# Main_Fly_V1_0_0.net
KiCad netlist of a schematic drawn in Altium Designer
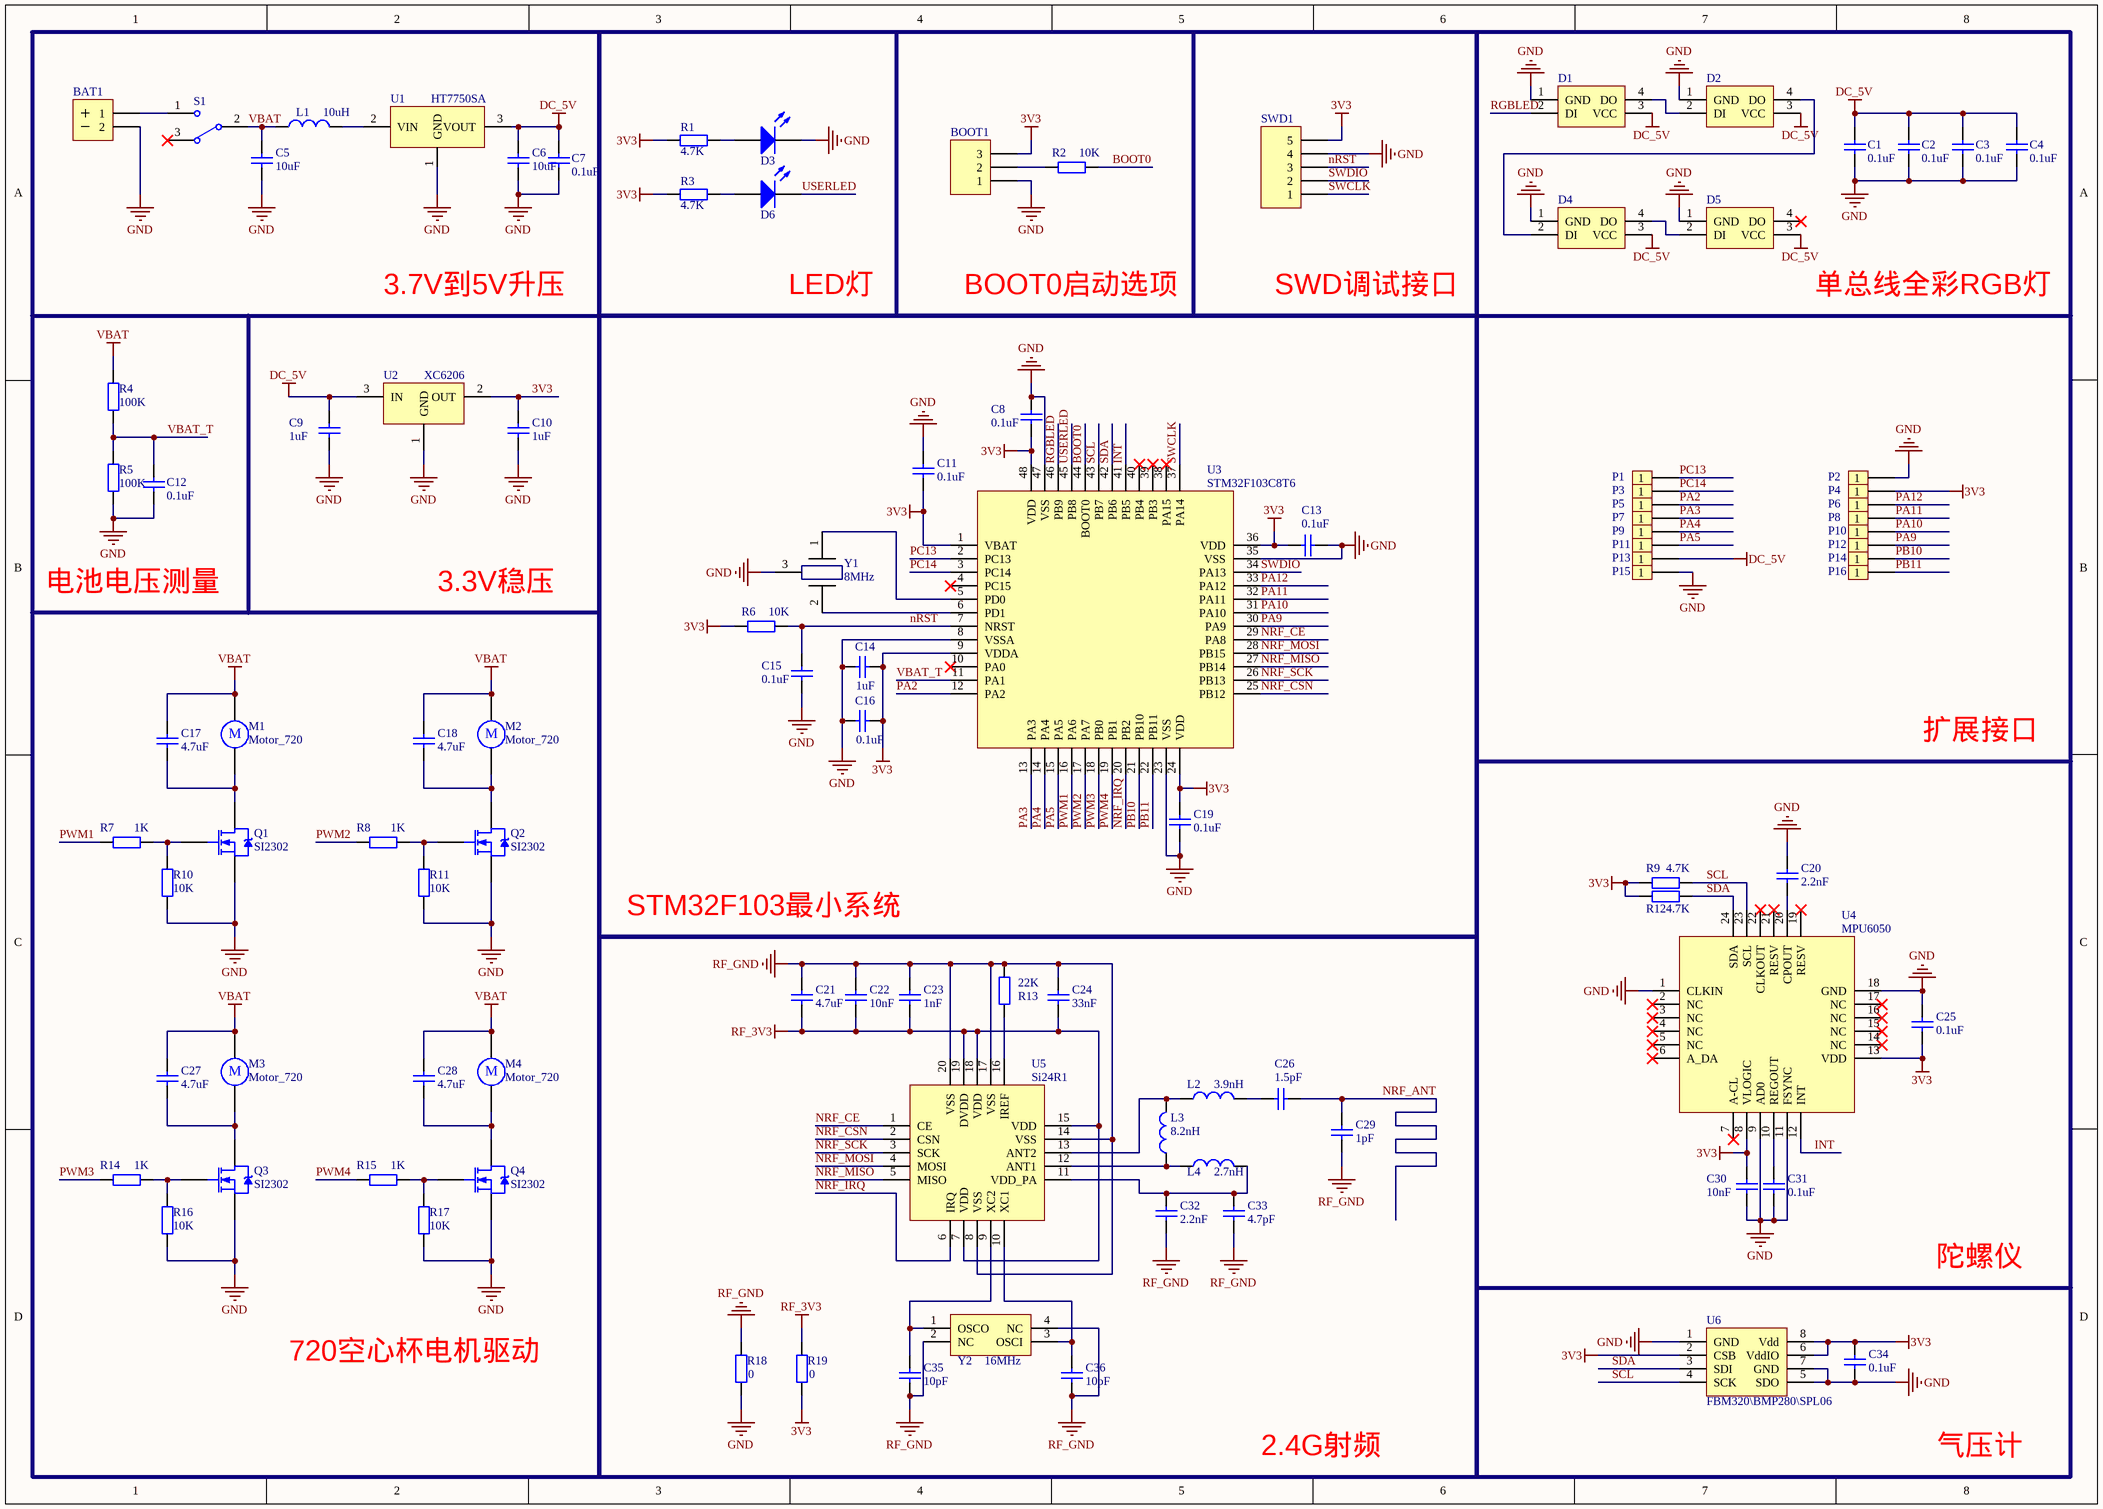
[diagram p0: Main_Fly_V1.0.0.SchDoc]

(export (version "E")
  (design (tool "Eeschema 10.0.6"))
  (components
    (comp (ref "BAT1")
      (value "BAT")
      (footprint "HDR1X2")
      (description "Header, 2-Pin")
      (fields (field (name "PUBLISHER") "mazhongwei"))
      (libsource (lib "RoboFly") (part "BAT"))
    )
    (comp (ref "BOOT1")
      (value "BOOT")
      (footprint "HDR1X3")
      (description "Header, 3-Pin")
      (fields (field (name "PUBLISHER") "Altium Limited"))
      (libsource (lib "RoboFly") (part "Header 3"))
    )
    (comp (ref "C1")
      (value "0.1uF")
      (footprint "C0603")
      (fields (field (name "Comment") "C_0603") (field (name "PUBLISHER") "Altium Limited"))
      (libsource (lib "RoboFly") (part "C_0603"))
    )
    (comp (ref "C2")
      (value "0.1uF")
      (footprint "C0603")
      (fields (field (name "Comment") "C_0603") (field (name "PUBLISHER") "Altium Limited"))
      (libsource (lib "RoboFly") (part "C_0603"))
    )
    (comp (ref "C3")
      (value "0.1uF")
      (footprint "C0603")
      (fields (field (name "Comment") "C_0603") (field (name "PUBLISHER") "Altium Limited"))
      (libsource (lib "RoboFly") (part "C_0603"))
    )
    (comp (ref "C4")
      (value "0.1uF")
      (footprint "C0603")
      (fields (field (name "Comment") "C_0603") (field (name "PUBLISHER") "Altium Limited"))
      (libsource (lib "RoboFly") (part "C_0603"))
    )
    (comp (ref "C5")
      (value "10uF")
      (footprint "C0603")
      (fields (field (name "Comment") "C_0603") (field (name "PUBLISHER") "Altium Limited"))
      (libsource (lib "RoboFly") (part "C_0603"))
    )
    (comp (ref "C6")
      (value "10uF")
      (footprint "C0603")
      (fields (field (name "Comment") "C_0603") (field (name "PUBLISHER") "Altium Limited"))
      (libsource (lib "RoboFly") (part "C_0603"))
    )
    (comp (ref "C7")
      (value "0.1uF")
      (footprint "C0603")
      (fields (field (name "Comment") "C_0603") (field (name "PUBLISHER") "Altium Limited"))
      (libsource (lib "RoboFly") (part "C_0603"))
    )
    (comp (ref "C8")
      (value "0.1uF")
      (footprint "C0603")
      (fields (field (name "Comment") "C_0603") (field (name "PUBLISHER") "Altium Limited"))
      (libsource (lib "RoboFly") (part "C_0603"))
    )
    (comp (ref "C9")
      (value "1uF")
      (footprint "C0603")
      (fields (field (name "Comment") "C_0603") (field (name "PUBLISHER") "Altium Limited"))
      (libsource (lib "RoboFly") (part "C_0603"))
    )
    (comp (ref "C10")
      (value "1uF")
      (footprint "C0603")
      (fields (field (name "Comment") "C_0603") (field (name "PUBLISHER") "Altium Limited"))
      (libsource (lib "RoboFly") (part "C_0603"))
    )
    (comp (ref "C11")
      (value "0.1uF")
      (footprint "C0603")
      (fields (field (name "Comment") "C_0603") (field (name "PUBLISHER") "Altium Limited"))
      (libsource (lib "RoboFly") (part "C_0603"))
    )
    (comp (ref "C12")
      (value "0.1uF")
      (footprint "C0603")
      (fields (field (name "Comment") "C_0603") (field (name "PUBLISHER") "Altium Limited"))
      (libsource (lib "RoboFly") (part "C_0603"))
    )
    (comp (ref "C13")
      (value "0.1uF")
      (footprint "C0603")
      (fields (field (name "Comment") "C_0603") (field (name "PUBLISHER") "Altium Limited"))
      (libsource (lib "RoboFly") (part "C_0603"))
    )
    (comp (ref "C14")
      (value "1uF")
      (footprint "C0603")
      (fields (field (name "Comment") "C_0603") (field (name "PUBLISHER") "Altium Limited"))
      (libsource (lib "RoboFly") (part "C_0603"))
    )
    (comp (ref "C15")
      (value "0.1uF")
      (footprint "C0603")
      (fields (field (name "Comment") "C_0603") (field (name "PUBLISHER") "Altium Limited"))
      (libsource (lib "RoboFly") (part "C_0603"))
    )
    (comp (ref "C16")
      (value "0.1uF")
      (footprint "C0603")
      (fields (field (name "Comment") "C_0603") (field (name "PUBLISHER") "Altium Limited"))
      (libsource (lib "RoboFly") (part "C_0603"))
    )
    (comp (ref "C17")
      (value "4.7uF")
      (footprint "C0603")
      (fields (field (name "Comment") "C_0603") (field (name "PUBLISHER") "Altium Limited"))
      (libsource (lib "RoboFly") (part "C_0603"))
    )
    (comp (ref "C18")
      (value "4.7uF")
      (footprint "C0603")
      (fields (field (name "Comment") "C_0603") (field (name "PUBLISHER") "Altium Limited"))
      (libsource (lib "RoboFly") (part "C_0603"))
    )
    (comp (ref "C19")
      (value "0.1uF")
      (footprint "C0603")
      (fields (field (name "Comment") "C_0603") (field (name "PUBLISHER") "Altium Limited"))
      (libsource (lib "RoboFly") (part "C_0603"))
    )
    (comp (ref "C20")
      (value "2.2nF")
      (footprint "C0603")
      (fields (field (name "Comment") "C_0603") (field (name "PUBLISHER") "Altium Limited"))
      (libsource (lib "RoboFly") (part "C_0603"))
    )
    (comp (ref "C21")
      (value "4.7uF")
      (footprint "C0603")
      (fields (field (name "Comment") "C_0603") (field (name "PUBLISHER") "Altium Limited"))
      (libsource (lib "RoboFly") (part "C_0603"))
    )
    (comp (ref "C22")
      (value "10nF")
      (footprint "C0603")
      (fields (field (name "Comment") "C_0603") (field (name "PUBLISHER") "Altium Limited"))
      (libsource (lib "RoboFly") (part "C_0603"))
    )
    (comp (ref "C23")
      (value "1nF")
      (footprint "C0603")
      (fields (field (name "Comment") "C_0603") (field (name "PUBLISHER") "Altium Limited"))
      (libsource (lib "RoboFly") (part "C_0603"))
    )
    (comp (ref "C24")
      (value "33nF")
      (footprint "C0603")
      (fields (field (name "Comment") "C_0603") (field (name "PUBLISHER") "Altium Limited"))
      (libsource (lib "RoboFly") (part "C_0603"))
    )
    (comp (ref "C25")
      (value "0.1uF")
      (footprint "C0603")
      (fields (field (name "Comment") "C_0603") (field (name "PUBLISHER") "Altium Limited"))
      (libsource (lib "RoboFly") (part "C_0603"))
    )
    (comp (ref "C26")
      (value "1.5pF")
      (footprint "C0603")
      (fields (field (name "Comment") "C_0603") (field (name "PUBLISHER") "Altium Limited"))
      (libsource (lib "RoboFly") (part "C_0603"))
    )
    (comp (ref "C27")
      (value "4.7uF")
      (footprint "C0603")
      (fields (field (name "Comment") "C_0603") (field (name "PUBLISHER") "Altium Limited"))
      (libsource (lib "RoboFly") (part "C_0603"))
    )
    (comp (ref "C28")
      (value "4.7uF")
      (footprint "C0603")
      (fields (field (name "Comment") "C_0603") (field (name "PUBLISHER") "Altium Limited"))
      (libsource (lib "RoboFly") (part "C_0603"))
    )
    (comp (ref "C29")
      (value "1pF")
      (footprint "C0603")
      (fields (field (name "Comment") "C_0603") (field (name "PUBLISHER") "Altium Limited"))
      (libsource (lib "RoboFly") (part "C_0603"))
    )
    (comp (ref "C30")
      (value "10nF")
      (footprint "C0603")
      (fields (field (name "Comment") "C_0603") (field (name "PUBLISHER") "Altium Limited"))
      (libsource (lib "RoboFly") (part "C_0603"))
    )
    (comp (ref "C31")
      (value "0.1uF")
      (footprint "C0603")
      (fields (field (name "Comment") "C_0603") (field (name "PUBLISHER") "Altium Limited"))
      (libsource (lib "RoboFly") (part "C_0603"))
    )
    (comp (ref "C32")
      (value "2.2nF")
      (footprint "C0603")
      (fields (field (name "Comment") "C_0603") (field (name "PUBLISHER") "Altium Limited"))
      (libsource (lib "RoboFly") (part "C_0603"))
    )
    (comp (ref "C33")
      (value "4.7pF")
      (footprint "C0603")
      (fields (field (name "Comment") "C_0603") (field (name "PUBLISHER") "Altium Limited"))
      (libsource (lib "RoboFly") (part "C_0603"))
    )
    (comp (ref "C34")
      (value "0.1uF")
      (footprint "C0603")
      (fields (field (name "Comment") "C_0603") (field (name "PUBLISHER") "Altium Limited"))
      (libsource (lib "RoboFly") (part "C_0603"))
    )
    (comp (ref "C35")
      (value "10pF")
      (footprint "C0603")
      (fields (field (name "Comment") "C_0603") (field (name "PUBLISHER") "Altium Limited"))
      (libsource (lib "RoboFly") (part "C_0603"))
    )
    (comp (ref "C36")
      (value "10pF")
      (footprint "C0603")
      (fields (field (name "Comment") "C_0603") (field (name "PUBLISHER") "Altium Limited"))
      (libsource (lib "RoboFly") (part "C_0603"))
    )
    (comp (ref "D1")
      (value "P923D")
      (footprint "RGB_LED_5050")
      (fields (field (name "PUBLISHER") "mazhongwei"))
      (libsource (lib "RoboFly") (part "P923D"))
    )
    (comp (ref "D2")
      (value "P923D")
      (footprint "RGB_LED_5050")
      (fields (field (name "PUBLISHER") "mazhongwei"))
      (libsource (lib "RoboFly") (part "P923D"))
    )
    (comp (ref "D3")
      (value "LED_0603")
      (footprint "LED0603-green")
      (description "发光二极管")
      (fields (field (name "PUBLISHER") "Altium Limited"))
      (libsource (lib "RoboFly") (part "LED 0603"))
    )
    (comp (ref "D4")
      (value "P923D")
      (footprint "RGB_LED_5050")
      (fields (field (name "PUBLISHER") "mazhongwei"))
      (libsource (lib "RoboFly") (part "P923D"))
    )
    (comp (ref "D5")
      (value "P923D")
      (footprint "RGB_LED_5050")
      (fields (field (name "PUBLISHER") "mazhongwei"))
      (libsource (lib "RoboFly") (part "P923D"))
    )
    (comp (ref "D6")
      (value "LED_0603")
      (footprint "LED0603-green")
      (description "发光二极管")
      (fields (field (name "PUBLISHER") "Altium Limited"))
      (libsource (lib "RoboFly") (part "LED 0603"))
    )
    (comp (ref "L1")
      (value "10uH")
      (footprint "L_1812")
      (description "电感")
      (fields (field (name "Comment") "Inductor") (field (name "PUBLISHER") "Altium Limited"))
      (libsource (lib "RoboFly") (part "Inductor"))
    )
    (comp (ref "L2")
      (value "3.9nH")
      (footprint "C0603")
      (description "电感")
      (fields (field (name "Comment") "Inductor") (field (name "PUBLISHER") "Altium Limited"))
      (libsource (lib "RoboFly") (part "Inductor_1"))
    )
    (comp (ref "L3")
      (value "8.2nH")
      (footprint "C0603")
      (description "电感")
      (fields (field (name "Comment") "Inductor") (field (name "PUBLISHER") "Altium Limited"))
      (libsource (lib "RoboFly") (part "Inductor_1"))
    )
    (comp (ref "L4")
      (value "2.7nH")
      (footprint "C0603")
      (description "电感")
      (fields (field (name "Comment") "Inductor") (field (name "PUBLISHER") "Altium Limited"))
      (libsource (lib "RoboFly") (part "Inductor_1"))
    )
    (comp (ref "M1")
      (value "Motor_720")
      (footprint "MOTOR")
      (description "Motor, General Kind")
      (fields (field (name "PUBLISHER") "mazhongwei"))
      (libsource (lib "RoboFly") (part "Motor_720"))
    )
    (comp (ref "M2")
      (value "Motor_720")
      (footprint "MOTOR")
      (description "Motor, General Kind")
      (fields (field (name "PUBLISHER") "mazhongwei"))
      (libsource (lib "RoboFly") (part "Motor_720"))
    )
    (comp (ref "M3")
      (value "Motor_720")
      (footprint "MOTOR")
      (description "Motor, General Kind")
      (fields (field (name "PUBLISHER") "mazhongwei"))
      (libsource (lib "RoboFly") (part "Motor_720"))
    )
    (comp (ref "M4")
      (value "Motor_720")
      (footprint "MOTOR")
      (description "Motor, General Kind")
      (fields (field (name "PUBLISHER") "mazhongwei"))
      (libsource (lib "RoboFly") (part "Motor_720"))
    )
    (comp (ref "P1")
      (value "Header 1")
      (footprint "HEADER1")
      (fields (field (name "PUBLISHER") "Altium Limited"))
      (libsource (lib "RoboFly") (part "Header 1"))
    )
    (comp (ref "P2")
      (value "Header 1")
      (footprint "HEADER1")
      (fields (field (name "PUBLISHER") "Altium Limited"))
      (libsource (lib "RoboFly") (part "Header 1"))
    )
    (comp (ref "P3")
      (value "Header 1")
      (footprint "HEADER1")
      (fields (field (name "PUBLISHER") "Altium Limited"))
      (libsource (lib "RoboFly") (part "Header 1"))
    )
    (comp (ref "P4")
      (value "Header 1")
      (footprint "HEADER1")
      (fields (field (name "PUBLISHER") "Altium Limited"))
      (libsource (lib "RoboFly") (part "Header 1"))
    )
    (comp (ref "P5")
      (value "Header 1")
      (footprint "HEADER1")
      (fields (field (name "PUBLISHER") "Altium Limited"))
      (libsource (lib "RoboFly") (part "Header 1"))
    )
    (comp (ref "P6")
      (value "Header 1")
      (footprint "HEADER1")
      (fields (field (name "PUBLISHER") "Altium Limited"))
      (libsource (lib "RoboFly") (part "Header 1"))
    )
    (comp (ref "P7")
      (value "Header 1")
      (footprint "HEADER1")
      (fields (field (name "PUBLISHER") "Altium Limited"))
      (libsource (lib "RoboFly") (part "Header 1"))
    )
    (comp (ref "P8")
      (value "Header 1")
      (footprint "HEADER1")
      (fields (field (name "PUBLISHER") "Altium Limited"))
      (libsource (lib "RoboFly") (part "Header 1"))
    )
    (comp (ref "P9")
      (value "Header 1")
      (footprint "HEADER1")
      (fields (field (name "PUBLISHER") "Altium Limited"))
      (libsource (lib "RoboFly") (part "Header 1"))
    )
    (comp (ref "P10")
      (value "Header 1")
      (footprint "HEADER1")
      (fields (field (name "PUBLISHER") "Altium Limited"))
      (libsource (lib "RoboFly") (part "Header 1"))
    )
    (comp (ref "P11")
      (value "Header 1")
      (footprint "HEADER1")
      (fields (field (name "PUBLISHER") "Altium Limited"))
      (libsource (lib "RoboFly") (part "Header 1"))
    )
    (comp (ref "P12")
      (value "Header 1")
      (footprint "HEADER1")
      (fields (field (name "PUBLISHER") "Altium Limited"))
      (libsource (lib "RoboFly") (part "Header 1"))
    )
    (comp (ref "P13")
      (value "Header 1")
      (footprint "HEADER1")
      (fields (field (name "PUBLISHER") "Altium Limited"))
      (libsource (lib "RoboFly") (part "Header 1"))
    )
    (comp (ref "P14")
      (value "Header 1")
      (footprint "HEADER1")
      (fields (field (name "PUBLISHER") "Altium Limited"))
      (libsource (lib "RoboFly") (part "Header 1"))
    )
    (comp (ref "P15")
      (value "Header 1")
      (footprint "HEADER1")
      (fields (field (name "PUBLISHER") "Altium Limited"))
      (libsource (lib "RoboFly") (part "Header 1"))
    )
    (comp (ref "P16")
      (value "Header 1")
      (footprint "HEADER1")
      (fields (field (name "PUBLISHER") "Altium Limited"))
      (libsource (lib "RoboFly") (part "Header 1"))
    )
    (comp (ref "Q1")
      (value "SI2302")
      (footprint "SOT-23-3")
      (description "N-Channel Power MOSFET")
      (fields (field (name "PUBLISHER") "mazhongwei"))
      (libsource (lib "RoboFly") (part "SI2302"))
    )
    (comp (ref "Q2")
      (value "SI2302")
      (footprint "SOT-23-3")
      (description "N-Channel Power MOSFET")
      (fields (field (name "PUBLISHER") "mazhongwei"))
      (libsource (lib "RoboFly") (part "SI2302"))
    )
    (comp (ref "Q3")
      (value "SI2302")
      (footprint "SOT-23-3")
      (description "N-Channel Power MOSFET")
      (fields (field (name "PUBLISHER") "mazhongwei"))
      (libsource (lib "RoboFly") (part "SI2302"))
    )
    (comp (ref "Q4")
      (value "SI2302")
      (footprint "SOT-23-3")
      (description "N-Channel Power MOSFET")
      (fields (field (name "PUBLISHER") "mazhongwei"))
      (libsource (lib "RoboFly") (part "SI2302"))
    )
    (comp (ref "R1")
      (value "4.7K")
      (footprint "R0603 - 1")
      (fields (field (name "Comment") "R_0603") (field (name "PUBLISHER") "Altium Limited"))
      (libsource (lib "RoboFly") (part "R_0603"))
    )
    (comp (ref "R2")
      (value "10K")
      (footprint "R0603 - 1")
      (fields (field (name "Comment") "R_0603") (field (name "PUBLISHER") "Altium Limited"))
      (libsource (lib "RoboFly") (part "R_0603"))
    )
    (comp (ref "R3")
      (value "4.7K")
      (footprint "R0603 - 1")
      (fields (field (name "Comment") "R_0603") (field (name "PUBLISHER") "Altium Limited"))
      (libsource (lib "RoboFly") (part "R_0603"))
    )
    (comp (ref "R4")
      (value "100K")
      (footprint "R0603 - 1")
      (fields (field (name "Comment") "R_0603") (field (name "PUBLISHER") "Altium Limited"))
      (libsource (lib "") (part "R_0603_1"))
    )
    (comp (ref "R5")
      (value "100K")
      (footprint "R0603 - 1")
      (fields (field (name "Comment") "R_0603") (field (name "PUBLISHER") "Altium Limited"))
      (libsource (lib "") (part "R_0603_1"))
    )
    (comp (ref "R6")
      (value "10K")
      (footprint "R0603 - 1")
      (fields (field (name "Comment") "R_0603") (field (name "PUBLISHER") "Altium Limited"))
      (libsource (lib "") (part "R_0603_2"))
    )
    (comp (ref "R7")
      (value "1K")
      (footprint "R0603 - 1")
      (fields (field (name "Comment") "R_0603") (field (name "PUBLISHER") "Altium Limited"))
      (libsource (lib "RoboFly") (part "R_0603"))
    )
    (comp (ref "R8")
      (value "1K")
      (footprint "R0603 - 1")
      (fields (field (name "Comment") "R_0603") (field (name "PUBLISHER") "Altium Limited"))
      (libsource (lib "RoboFly") (part "R_0603"))
    )
    (comp (ref "R9")
      (value "4.7K")
      (footprint "R0603 - 1")
      (fields (field (name "Comment") "R_0603") (field (name "PUBLISHER") "Altium Limited"))
      (libsource (lib "RoboFly") (part "R_0603"))
    )
    (comp (ref "R10")
      (value "10K")
      (footprint "R0603 - 1")
      (fields (field (name "Comment") "R_0603") (field (name "PUBLISHER") "Altium Limited"))
      (libsource (lib "") (part "R_0603_1"))
    )
    (comp (ref "R11")
      (value "10K")
      (footprint "R0603 - 1")
      (fields (field (name "Comment") "R_0603") (field (name "PUBLISHER") "Altium Limited"))
      (libsource (lib "") (part "R_0603_1"))
    )
    (comp (ref "R12")
      (value "4.7K")
      (footprint "R0603 - 1")
      (fields (field (name "Comment") "R_0603") (field (name "PUBLISHER") "Altium Limited"))
      (libsource (lib "RoboFly") (part "R_0603"))
    )
    (comp (ref "R13")
      (value "22K")
      (footprint "R0603 - 1")
      (fields (field (name "Comment") "R_0603") (field (name "PUBLISHER") "Altium Limited"))
      (libsource (lib "") (part "R_0603_1"))
    )
    (comp (ref "R14")
      (value "1K")
      (footprint "R0603 - 1")
      (fields (field (name "Comment") "R_0603") (field (name "PUBLISHER") "Altium Limited"))
      (libsource (lib "RoboFly") (part "R_0603"))
    )
    (comp (ref "R15")
      (value "1K")
      (footprint "R0603 - 1")
      (fields (field (name "Comment") "R_0603") (field (name "PUBLISHER") "Altium Limited"))
      (libsource (lib "RoboFly") (part "R_0603"))
    )
    (comp (ref "R16")
      (value "10K")
      (footprint "R0603 - 1")
      (fields (field (name "Comment") "R_0603") (field (name "PUBLISHER") "Altium Limited"))
      (libsource (lib "") (part "R_0603_1"))
    )
    (comp (ref "R17")
      (value "10K")
      (footprint "R0603 - 1")
      (fields (field (name "Comment") "R_0603") (field (name "PUBLISHER") "Altium Limited"))
      (libsource (lib "") (part "R_0603_1"))
    )
    (comp (ref "R18")
      (value "0")
      (footprint "R0603 - 1")
      (fields (field (name "Comment") "R_0603") (field (name "PUBLISHER") "Altium Limited"))
      (libsource (lib "新版四轴飞行器") (part "R_0603"))
    )
    (comp (ref "R19")
      (value "0")
      (footprint "R0603 - 1")
      (fields (field (name "Comment") "R_0603") (field (name "PUBLISHER") "Altium Limited"))
      (libsource (lib "新版四轴飞行器") (part "R_0603"))
    )
    (comp (ref "S1")
      (value "SW-SPDT")
      (footprint "SWITCH_PWR")
      (description "SPDT Subminiature Toggle Switch, Right Angle Mounting, Vertical Actuation")
      (fields (field (name "PUBLISHER") "mazhongwei"))
      (libsource (lib "RoboFly") (part "SW-SPDT"))
    )
    (comp (ref "SWD1")
      (value "SWD")
      (footprint "HDR1X5")
      (description "Header, 5-Pin")
      (fields (field (name "PUBLISHER") "Altium Limited"))
      (libsource (lib "RoboFly") (part "Header 5"))
    )
    (comp (ref "U1")
      (value "HT7750SA")
      (footprint "SOT-89(SOT-89-3)")
      (libsource (lib "RoboFly") (part "HT7750SA"))
    )
    (comp (ref "U2")
      (value "XC6206")
      (footprint "SOT-23-3")
      (fields (field (name "PUBLISHER") "mazhongwei"))
      (libsource (lib "RoboFly") (part "XC6206"))
    )
    (comp (ref "U3")
      (value "STM32F103C8T6")
      (footprint "LC-LQFP-48_7x7x05P")
      (libsource (lib "RoboFly") (part "STM32F103C8T6"))
    )
    (comp (ref "U4")
      (value "MPU6050")
      (footprint "QFN-24_4x4x05P")
      (libsource (lib "RoboFly") (part "MPU6050"))
    )
    (comp (ref "U5") (value "Si24R1") (footprint "QFN-20_4x4") (libsource (lib "RoboFly") (part "nRF24L01")))
    (comp (ref "U6")
      (value "FBM32~{0}BMP28~{0}SPL06")
      (footprint "LGA-2_5X2MM")
      (description "气压计")
      (fields (field (name "PUBLISHER") "mazhongwei"))
      (libsource (lib "RoboFly") (part "FBM320"))
    )
    (comp (ref "Y1")
      (value "8MHz")
      (footprint "SMD-cstse800G52-r0")
      (fields (field (name "Comment") "XTAL") (field (name "PUBLISHER") "mazhongwei"))
      (libsource (lib "RoboFly") (part "XTAL_2"))
    )
    (comp (ref "Y2")
      (value "16MHz")
      (footprint "CRYSTAL_RSX-10")
      (description "XTAL16M")
      (fields (field (name "Comment") "XTAL"))
      (libsource (lib "RoboFly") (part "XTAL16M"))
    )
  )
  (nets
    (net (code "1") (name "/BOOT0") (class "Default")
      (node (ref "R2") (pin "2") (pinfunction "2_2") (pintype "passive"))
      (node (ref "U3") (pin "44") (pinfunction "BOOT0_44") (pintype "passive"))
    )
    (net (code "2") (name "/INT") (class "Default")
      (node (ref "U3") (pin "41") (pinfunction "PB5_41") (pintype "passive"))
      (node (ref "U4") (pin "12") (pinfunction "INT_12") (pintype "passive"))
    )
    (net (code "3") (name "/NRF_ANT") (class "Default")
      (node (ref "C26") (pin "2") (pinfunction "2_2") (pintype "passive"))
      (node (ref "C29") (pin "2") (pinfunction "2_2") (pintype "passive"))
    )
    (net (code "4") (name "/NRF_CE") (class "Default")
      (node (ref "U3") (pin "29") (pinfunction "PA8_29") (pintype "passive"))
      (node (ref "U5") (pin "1") (pinfunction "CE_1") (pintype "passive"))
    )
    (net (code "5") (name "/NRF_CSN") (class "Default")
      (node (ref "U3") (pin "25") (pinfunction "PB12_25") (pintype "passive"))
      (node (ref "U5") (pin "2") (pinfunction "CSN_2") (pintype "passive"))
    )
    (net (code "6") (name "/NRF_IRQ") (class "Default")
      (node (ref "U3") (pin "20") (pinfunction "PB2_20") (pintype "passive"))
      (node (ref "U5") (pin "6") (pinfunction "IRQ_6") (pintype "passive"))
    )
    (net (code "7") (name "/NRF_MISO") (class "Default")
      (node (ref "U3") (pin "27") (pinfunction "PB14_27") (pintype "passive"))
      (node (ref "U5") (pin "5") (pinfunction "MISO_5") (pintype "passive"))
    )
    (net (code "8") (name "/NRF_MOSI") (class "Default")
      (node (ref "U3") (pin "28") (pinfunction "PB15_28") (pintype "passive"))
      (node (ref "U5") (pin "4") (pinfunction "MOSI_4") (pintype "passive"))
    )
    (net (code "9") (name "/NRF_SCK") (class "Default")
      (node (ref "U3") (pin "26") (pinfunction "PB13_26") (pintype "passive"))
      (node (ref "U5") (pin "3") (pinfunction "SCK_3") (pintype "passive"))
    )
    (net (code "10") (name "/PA2") (class "Default")
      (node (ref "P5") (pin "1") (pinfunction "1_1") (pintype "passive"))
      (node (ref "U3") (pin "12") (pinfunction "PA2_12") (pintype "passive"))
    )
    (net (code "11") (name "/PA3") (class "Default")
      (node (ref "P7") (pin "1") (pinfunction "1_1") (pintype "passive"))
      (node (ref "U3") (pin "13") (pinfunction "PA3_13") (pintype "passive"))
    )
    (net (code "12") (name "/PA4") (class "Default")
      (node (ref "P9") (pin "1") (pinfunction "1_1") (pintype "passive"))
      (node (ref "U3") (pin "14") (pinfunction "PA4_14") (pintype "passive"))
    )
    (net (code "13") (name "/PA5") (class "Default")
      (node (ref "P11") (pin "1") (pinfunction "1_1") (pintype "passive"))
      (node (ref "U3") (pin "15") (pinfunction "PA5_15") (pintype "passive"))
    )
    (net (code "14") (name "/PA9") (class "Default")
      (node (ref "P12") (pin "1") (pinfunction "1_1") (pintype "passive"))
      (node (ref "U3") (pin "30") (pinfunction "PA9_30") (pintype "passive"))
    )
    (net (code "15") (name "/PA10") (class "Default")
      (node (ref "P10") (pin "1") (pinfunction "1_1") (pintype "passive"))
      (node (ref "U3") (pin "31") (pinfunction "PA10_31") (pintype "passive"))
    )
    (net (code "16") (name "/PA11") (class "Default")
      (node (ref "P8") (pin "1") (pinfunction "1_1") (pintype "passive"))
      (node (ref "U3") (pin "32") (pinfunction "PA11_32") (pintype "passive"))
    )
    (net (code "17") (name "/PA12") (class "Default")
      (node (ref "P6") (pin "1") (pinfunction "1_1") (pintype "passive"))
      (node (ref "U3") (pin "33") (pinfunction "PA12_33") (pintype "passive"))
    )
    (net (code "18") (name "/PB10") (class "Default")
      (node (ref "P14") (pin "1") (pinfunction "1_1") (pintype "passive"))
      (node (ref "U3") (pin "21") (pinfunction "PB10_21") (pintype "passive"))
    )
    (net (code "19") (name "/PB11") (class "Default")
      (node (ref "P16") (pin "1") (pinfunction "1_1") (pintype "passive"))
      (node (ref "U3") (pin "22") (pinfunction "PB11_22") (pintype "passive"))
    )
    (net (code "20") (name "/PC13") (class "Default")
      (node (ref "P1") (pin "1") (pinfunction "1_1") (pintype "passive"))
      (node (ref "U3") (pin "2") (pinfunction "PC13_2") (pintype "passive"))
    )
    (net (code "21") (name "/PC14") (class "Default")
      (node (ref "P3") (pin "1") (pinfunction "1_1") (pintype "passive"))
      (node (ref "U3") (pin "3") (pinfunction "PC14_3") (pintype "passive"))
    )
    (net (code "22") (name "/PWM1") (class "Default")
      (node (ref "R7") (pin "1") (pinfunction "1_1") (pintype "passive"))
      (node (ref "U3") (pin "16") (pinfunction "PA6_16") (pintype "passive"))
    )
    (net (code "23") (name "/PWM2") (class "Default")
      (node (ref "R8") (pin "1") (pinfunction "1_1") (pintype "passive"))
      (node (ref "U3") (pin "17") (pinfunction "PA7_17") (pintype "passive"))
    )
    (net (code "24") (name "/PWM3") (class "Default")
      (node (ref "R14") (pin "1") (pinfunction "1_1") (pintype "passive"))
      (node (ref "U3") (pin "18") (pinfunction "PB0_18") (pintype "passive"))
    )
    (net (code "25") (name "/PWM4") (class "Default")
      (node (ref "R15") (pin "1") (pinfunction "1_1") (pintype "passive"))
      (node (ref "U3") (pin "19") (pinfunction "PB1_19") (pintype "passive"))
    )
    (net (code "26") (name "/RGBLED") (class "Default")
      (node (ref "D1") (pin "2") (pinfunction "DI_2") (pintype "passive"))
      (node (ref "U3") (pin "46") (pinfunction "PB9_46") (pintype "passive"))
    )
    (net (code "27") (name "/SCL") (class "Default")
      (node (ref "R9") (pin "2") (pinfunction "2_2") (pintype "passive"))
      (node (ref "U3") (pin "43") (pinfunction "PB7_43") (pintype "passive"))
      (node (ref "U4") (pin "23") (pinfunction "SCL_23") (pintype "passive"))
      (node (ref "U6") (pin "4") (pinfunction "SCK_4") (pintype "passive"))
    )
    (net (code "28") (name "/SDA") (class "Default")
      (node (ref "R12") (pin "2") (pinfunction "2_2") (pintype "passive"))
      (node (ref "U3") (pin "42") (pinfunction "PB6_42") (pintype "passive"))
      (node (ref "U4") (pin "24") (pinfunction "SDA_24") (pintype "passive"))
      (node (ref "U6") (pin "3") (pinfunction "SDI_3") (pintype "passive"))
    )
    (net (code "29") (name "/SWCLK") (class "Default")
      (node (ref "SWD1") (pin "1") (pinfunction "1_1") (pintype "passive"))
      (node (ref "U3") (pin "37") (pinfunction "PA14_37") (pintype "passive"))
    )
    (net (code "30") (name "/SWDIO") (class "Default")
      (node (ref "SWD1") (pin "2") (pinfunction "2_2") (pintype "passive"))
      (node (ref "U3") (pin "34") (pinfunction "PA13_34") (pintype "passive"))
    )
    (net (code "31") (name "/USERLED") (class "Default")
      (node (ref "D6") (pin "2") (pinfunction "2_2") (pintype "passive"))
      (node (ref "U3") (pin "45") (pinfunction "PB8_45") (pintype "passive"))
    )
    (net (code "32") (name "/VBAT_T") (class "Default")
      (node (ref "C12") (pin "2") (pinfunction "2_2") (pintype "passive"))
      (node (ref "R4") (pin "1") (pinfunction "1_1") (pintype "passive"))
      (node (ref "R5") (pin "2") (pinfunction "2_2") (pintype "passive"))
      (node (ref "U3") (pin "11") (pinfunction "PA1_11") (pintype "passive"))
    )
    (net (code "33") (name "/nRST") (class "Default")
      (node (ref "C15") (pin "2") (pinfunction "2_2") (pintype "passive"))
      (node (ref "R6") (pin "1") (pinfunction "1_1") (pintype "passive"))
      (node (ref "SWD1") (pin "3") (pinfunction "3_3") (pintype "passive"))
      (node (ref "U3") (pin "7") (pinfunction "NRST_7") (pintype "passive"))
    )
    (net (code "34") (name "3V3") (class "Default")
      (node (ref "BOOT1") (pin "3") (pinfunction "3_3") (pintype "passive"))
      (node (ref "C10") (pin "1") (pinfunction "1_1") (pintype "passive"))
      (node (ref "C11") (pin "2") (pinfunction "2_2") (pintype "passive"))
      (node (ref "C13") (pin "2") (pinfunction "2_2") (pintype "passive"))
      (node (ref "C14") (pin "2") (pinfunction "2_2") (pintype "passive"))
      (node (ref "C16") (pin "2") (pinfunction "2_2") (pintype "passive"))
      (node (ref "C19") (pin "1") (pinfunction "1_1") (pintype "passive"))
      (node (ref "C25") (pin "2") (pinfunction "2_2") (pintype "passive"))
      (node (ref "C30") (pin "2") (pinfunction "2_2") (pintype "passive"))
      (node (ref "C34") (pin "1") (pinfunction "1_1") (pintype "passive"))
      (node (ref "C8") (pin "1") (pinfunction "1_1") (pintype "passive"))
      (node (ref "P4") (pin "1") (pinfunction "1_1") (pintype "passive"))
      (node (ref "R1") (pin "1") (pinfunction "1_1") (pintype "passive"))
      (node (ref "R12") (pin "1") (pinfunction "1_1") (pintype "passive"))
      (node (ref "R19") (pin "1") (pinfunction "1_1") (pintype "passive"))
      (node (ref "R3") (pin "1") (pinfunction "1_1") (pintype "passive"))
      (node (ref "R6") (pin "2") (pinfunction "2_2") (pintype "passive"))
      (node (ref "R9") (pin "1") (pinfunction "1_1") (pintype "passive"))
      (node (ref "SWD1") (pin "5") (pinfunction "5_5") (pintype "passive"))
      (node (ref "U2") (pin "2") (pinfunction "OUT_2") (pintype "passive"))
      (node (ref "U3") (pin "1") (pinfunction "VBAT_1") (pintype "passive"))
      (node (ref "U3") (pin "24") (pinfunction "VDD_24") (pintype "passive"))
      (node (ref "U3") (pin "36") (pinfunction "VDD_36") (pintype "passive"))
      (node (ref "U3") (pin "48") (pinfunction "VDD_48") (pintype "passive"))
      (node (ref "U3") (pin "9") (pinfunction "VDDA_9") (pintype "passive"))
      (node (ref "U4") (pin "13") (pinfunction "VDD_13") (pintype "passive"))
      (node (ref "U4") (pin "8") (pinfunction "VLOGIC_8") (pintype "passive"))
      (node (ref "U6") (pin "2") (pinfunction "CSB_2") (pintype "passive"))
      (node (ref "U6") (pin "6") (pinfunction "VddIO_6") (pintype "passive"))
      (node (ref "U6") (pin "8") (pinfunction "Vdd_8") (pintype "passive"))
    )
    (net (code "35") (name "DC_5V") (class "Default")
      (node (ref "C1") (pin "2") (pinfunction "2_2") (pintype "passive"))
      (node (ref "C2") (pin "2") (pinfunction "2_2") (pintype "passive"))
      (node (ref "C3") (pin "2") (pinfunction "2_2") (pintype "passive"))
      (node (ref "C4") (pin "2") (pinfunction "2_2") (pintype "passive"))
      (node (ref "C6") (pin "1") (pinfunction "1_1") (pintype "passive"))
      (node (ref "C7") (pin "2") (pinfunction "2_2") (pintype "passive"))
      (node (ref "C9") (pin "2") (pinfunction "2_2") (pintype "passive"))
      (node (ref "D1") (pin "3") (pinfunction "VCC_3") (pintype "passive"))
      (node (ref "D2") (pin "3") (pinfunction "VCC_3") (pintype "passive"))
      (node (ref "D4") (pin "3") (pinfunction "VCC_3") (pintype "passive"))
      (node (ref "D5") (pin "3") (pinfunction "VCC_3") (pintype "passive"))
      (node (ref "P13") (pin "1") (pinfunction "1_1") (pintype "passive"))
      (node (ref "U1") (pin "3") (pinfunction "VOUT_3") (pintype "passive"))
      (node (ref "U2") (pin "3") (pinfunction "IN_3") (pintype "passive"))
    )
    (net (code "36") (name "GND") (class "Default")
      (node (ref "BAT1") (pin "2") (pinfunction "2_2") (pintype "passive"))
      (node (ref "BOOT1") (pin "1") (pinfunction "1_1") (pintype "passive"))
      (node (ref "C1") (pin "1") (pinfunction "1_1") (pintype "passive"))
      (node (ref "C10") (pin "2") (pinfunction "2_2") (pintype "passive"))
      (node (ref "C11") (pin "1") (pinfunction "1_1") (pintype "passive"))
      (node (ref "C12") (pin "1") (pinfunction "1_1") (pintype "passive"))
      (node (ref "C13") (pin "1") (pinfunction "1_1") (pintype "passive"))
      (node (ref "C14") (pin "1") (pinfunction "1_1") (pintype "passive"))
      (node (ref "C15") (pin "1") (pinfunction "1_1") (pintype "passive"))
      (node (ref "C16") (pin "1") (pinfunction "1_1") (pintype "passive"))
      (node (ref "C19") (pin "2") (pinfunction "2_2") (pintype "passive"))
      (node (ref "C2") (pin "1") (pinfunction "1_1") (pintype "passive"))
      (node (ref "C20") (pin "1") (pinfunction "1_1") (pintype "passive"))
      (node (ref "C25") (pin "1") (pinfunction "1_1") (pintype "passive"))
      (node (ref "C3") (pin "1") (pinfunction "1_1") (pintype "passive"))
      (node (ref "C30") (pin "1") (pinfunction "1_1") (pintype "passive"))
      (node (ref "C31") (pin "2") (pinfunction "2_2") (pintype "passive"))
      (node (ref "C34") (pin "2") (pinfunction "2_2") (pintype "passive"))
      (node (ref "C4") (pin "1") (pinfunction "1_1") (pintype "passive"))
      (node (ref "C5") (pin "2") (pinfunction "2_2") (pintype "passive"))
      (node (ref "C6") (pin "2") (pinfunction "2_2") (pintype "passive"))
      (node (ref "C7") (pin "1") (pinfunction "1_1") (pintype "passive"))
      (node (ref "C8") (pin "2") (pinfunction "2_2") (pintype "passive"))
      (node (ref "C9") (pin "1") (pinfunction "1_1") (pintype "passive"))
      (node (ref "D1") (pin "1") (pinfunction "GND_1") (pintype "passive"))
      (node (ref "D2") (pin "1") (pinfunction "GND_1") (pintype "passive"))
      (node (ref "D3") (pin "2") (pinfunction "2_2") (pintype "passive"))
      (node (ref "D4") (pin "1") (pinfunction "GND_1") (pintype "passive"))
      (node (ref "D5") (pin "1") (pinfunction "GND_1") (pintype "passive"))
      (node (ref "P15") (pin "1") (pinfunction "1_1") (pintype "passive"))
      (node (ref "P2") (pin "1") (pinfunction "1_1") (pintype "passive"))
      (node (ref "Q1") (pin "2") (pinfunction "S_2") (pintype "passive"))
      (node (ref "Q2") (pin "2") (pinfunction "S_2") (pintype "passive"))
      (node (ref "Q3") (pin "2") (pinfunction "S_2") (pintype "passive"))
      (node (ref "Q4") (pin "2") (pinfunction "S_2") (pintype "passive"))
      (node (ref "R10") (pin "1") (pinfunction "1_1") (pintype "passive"))
      (node (ref "R11") (pin "1") (pinfunction "1_1") (pintype "passive"))
      (node (ref "R16") (pin "1") (pinfunction "1_1") (pintype "passive"))
      (node (ref "R17") (pin "1") (pinfunction "1_1") (pintype "passive"))
      (node (ref "R18") (pin "1") (pinfunction "1_1") (pintype "passive"))
      (node (ref "R5") (pin "1") (pinfunction "1_1") (pintype "passive"))
      (node (ref "SWD1") (pin "4") (pinfunction "4_4") (pintype "passive"))
      (node (ref "U1") (pin "1") (pinfunction "GND_1") (pintype "passive"))
      (node (ref "U2") (pin "1") (pinfunction "GND_1") (pintype "passive"))
      (node (ref "U3") (pin "23") (pinfunction "VSS_23") (pintype "passive"))
      (node (ref "U3") (pin "35") (pinfunction "VSS_35") (pintype "passive"))
      (node (ref "U3") (pin "47") (pinfunction "VSS_47") (pintype "passive"))
      (node (ref "U3") (pin "8") (pinfunction "VSSA_8") (pintype "passive"))
      (node (ref "U4") (pin "1") (pinfunction "CLKIN_1") (pintype "passive"))
      (node (ref "U4") (pin "11") (pinfunction "FSYNC_11") (pintype "passive"))
      (node (ref "U4") (pin "18") (pinfunction "GND_18") (pintype "passive"))
      (node (ref "U4") (pin "9") (pinfunction "AD0_9") (pintype "passive"))
      (node (ref "U6") (pin "1") (pinfunction "GND_1") (pintype "passive"))
      (node (ref "U6") (pin "5") (pinfunction "SDO_5") (pintype "passive"))
      (node (ref "U6") (pin "7") (pinfunction "GND_7") (pintype "passive"))
      (node (ref "Y1") (pin "3") (pinfunction "3_3") (pintype "passive"))
    )
    (net (code "37") (name "Net-(BAT1-Pad1)") (class "Default")
      (node (ref "BAT1") (pin "1") (pinfunction "1_1") (pintype "passive"))
      (node (ref "S1") (pin "1") (pinfunction "1_1") (pintype "passive"))
    )
    (net (code "38") (name "Net-(BOOT1-Pad2)") (class "Default")
      (node (ref "BOOT1") (pin "2") (pinfunction "2_2") (pintype "passive"))
      (node (ref "R2") (pin "1") (pinfunction "1_1") (pintype "passive"))
    )
    (net (code "39") (name "Net-(C26-Pad1)") (class "Default")
      (node (ref "C26") (pin "1") (pinfunction "1_1") (pintype "passive"))
      (node (ref "L2") (pin "2") (pinfunction "2_2") (pintype "passive"))
    )
    (net (code "40") (name "Net-(D1-DO)") (class "Default")
      (node (ref "D1") (pin "4") (pinfunction "DO_4") (pintype "passive"))
      (node (ref "D2") (pin "2") (pinfunction "DI_2") (pintype "passive"))
    )
    (net (code "41") (name "Net-(D2-DO)") (class "Default")
      (node (ref "D2") (pin "4") (pinfunction "DO_4") (pintype "passive"))
      (node (ref "D4") (pin "2") (pinfunction "DI_2") (pintype "passive"))
    )
    (net (code "42") (name "Net-(D3-Pad1)") (class "Default")
      (node (ref "D3") (pin "1") (pinfunction "1_1") (pintype "passive"))
      (node (ref "R1") (pin "2") (pinfunction "2_2") (pintype "passive"))
    )
    (net (code "43") (name "Net-(D4-DO)") (class "Default")
      (node (ref "D4") (pin "4") (pinfunction "DO_4") (pintype "passive"))
      (node (ref "D5") (pin "2") (pinfunction "DI_2") (pintype "passive"))
    )
    (net (code "44") (name "Net-(D6-Pad1)") (class "Default")
      (node (ref "D6") (pin "1") (pinfunction "1_1") (pintype "passive"))
      (node (ref "R3") (pin "2") (pinfunction "2_2") (pintype "passive"))
    )
    (net (code "45") (name "Net-(Q1-D)") (class "Default")
      (node (ref "C17") (pin "1") (pinfunction "1_1") (pintype "passive"))
      (node (ref "M1") (pin "2") (pinfunction "2_2") (pintype "passive"))
      (node (ref "Q1") (pin "3") (pinfunction "D_3") (pintype "passive"))
    )
    (net (code "46") (name "Net-(Q1-G)") (class "Default")
      (node (ref "Q1") (pin "1") (pinfunction "G_1") (pintype "passive"))
      (node (ref "R10") (pin "2") (pinfunction "2_2") (pintype "passive"))
      (node (ref "R7") (pin "2") (pinfunction "2_2") (pintype "passive"))
    )
    (net (code "47") (name "Net-(Q2-D)") (class "Default")
      (node (ref "C18") (pin "1") (pinfunction "1_1") (pintype "passive"))
      (node (ref "M2") (pin "2") (pinfunction "2_2") (pintype "passive"))
      (node (ref "Q2") (pin "3") (pinfunction "D_3") (pintype "passive"))
    )
    (net (code "48") (name "Net-(Q2-G)") (class "Default")
      (node (ref "Q2") (pin "1") (pinfunction "G_1") (pintype "passive"))
      (node (ref "R11") (pin "2") (pinfunction "2_2") (pintype "passive"))
      (node (ref "R8") (pin "2") (pinfunction "2_2") (pintype "passive"))
    )
    (net (code "49") (name "Net-(Q3-D)") (class "Default")
      (node (ref "C27") (pin "1") (pinfunction "1_1") (pintype "passive"))
      (node (ref "M3") (pin "2") (pinfunction "2_2") (pintype "passive"))
      (node (ref "Q3") (pin "3") (pinfunction "D_3") (pintype "passive"))
    )
    (net (code "50") (name "Net-(Q3-G)") (class "Default")
      (node (ref "Q3") (pin "1") (pinfunction "G_1") (pintype "passive"))
      (node (ref "R14") (pin "2") (pinfunction "2_2") (pintype "passive"))
      (node (ref "R16") (pin "2") (pinfunction "2_2") (pintype "passive"))
    )
    (net (code "51") (name "Net-(Q4-D)") (class "Default")
      (node (ref "C28") (pin "1") (pinfunction "1_1") (pintype "passive"))
      (node (ref "M4") (pin "2") (pinfunction "2_2") (pintype "passive"))
      (node (ref "Q4") (pin "3") (pinfunction "D_3") (pintype "passive"))
    )
    (net (code "52") (name "Net-(Q4-G)") (class "Default")
      (node (ref "Q4") (pin "1") (pinfunction "G_1") (pintype "passive"))
      (node (ref "R15") (pin "2") (pinfunction "2_2") (pintype "passive"))
      (node (ref "R17") (pin "2") (pinfunction "2_2") (pintype "passive"))
    )
    (net (code "53") (name "Net-(U1-VIN)") (class "Default")
      (node (ref "L1") (pin "2") (pinfunction "2_2") (pintype "passive"))
      (node (ref "U1") (pin "2") (pinfunction "VIN_2") (pintype "passive"))
    )
    (net (code "54") (name "Net-(U3-PD0)") (class "Default")
      (node (ref "U3") (pin "5") (pinfunction "PD0_5") (pintype "passive"))
      (node (ref "Y1") (pin "1") (pinfunction "1_1") (pintype "passive"))
    )
    (net (code "55") (name "Net-(U3-PD1)") (class "Default")
      (node (ref "U3") (pin "6") (pinfunction "PD1_6") (pintype "passive"))
      (node (ref "Y1") (pin "2") (pinfunction "2_2") (pintype "passive"))
    )
    (net (code "56") (name "Net-(U4-CPOUT)") (class "Default")
      (node (ref "C20") (pin "2") (pinfunction "2_2") (pintype "passive"))
      (node (ref "U4") (pin "20") (pinfunction "CPOUT_20") (pintype "passive"))
    )
    (net (code "57") (name "Net-(U4-REGOUT)") (class "Default")
      (node (ref "C31") (pin "1") (pinfunction "1_1") (pintype "passive"))
      (node (ref "U4") (pin "10") (pinfunction "REGOUT_10") (pintype "passive"))
    )
    (net (code "58") (name "Net-(U5-ANT1)") (class "Default")
      (node (ref "L3") (pin "1") (pinfunction "1_1") (pintype "passive"))
      (node (ref "L4") (pin "1") (pinfunction "1_1") (pintype "passive"))
      (node (ref "U5") (pin "12") (pinfunction "ANT1_12") (pintype "passive"))
    )
    (net (code "59") (name "Net-(U5-ANT2)") (class "Default")
      (node (ref "L2") (pin "1") (pinfunction "1_1") (pintype "passive"))
      (node (ref "L3") (pin "2") (pinfunction "2_2") (pintype "passive"))
      (node (ref "U5") (pin "13") (pinfunction "ANT2_13") (pintype "passive"))
    )
    (net (code "60") (name "Net-(U5-IREF)") (class "Default")
      (node (ref "R13") (pin "1") (pinfunction "1_1") (pintype "passive"))
      (node (ref "U5") (pin "16") (pinfunction "IREF_16") (pintype "passive"))
    )
    (net (code "61") (name "Net-(U5-VDD_PA)") (class "Default")
      (node (ref "C32") (pin "2") (pinfunction "2_2") (pintype "passive"))
      (node (ref "C33") (pin "2") (pinfunction "2_2") (pintype "passive"))
      (node (ref "L4") (pin "2") (pinfunction "2_2") (pintype "passive"))
      (node (ref "U5") (pin "11") (pinfunction "VDD_PA_11") (pintype "passive"))
    )
    (net (code "62") (name "Net-(U5-XC1)") (class "Default")
      (node (ref "C36") (pin "2") (pinfunction "2_2") (pintype "passive"))
      (node (ref "U5") (pin "10") (pinfunction "XC1_10") (pintype "passive"))
      (node (ref "Y2") (pin "3") (pinfunction "OSCI_3") (pintype "passive"))
    )
    (net (code "63") (name "Net-(U5-XC2)") (class "Default")
      (node (ref "C35") (pin "2") (pinfunction "2_2") (pintype "passive"))
      (node (ref "U5") (pin "9") (pinfunction "XC2_9") (pintype "passive"))
      (node (ref "Y2") (pin "1") (pinfunction "OSCO_1") (pintype "passive"))
    )
    (net (code "64") (name "RF_3V3") (class "Default")
      (node (ref "C21") (pin "1") (pinfunction "1_1") (pintype "passive"))
      (node (ref "C22") (pin "1") (pinfunction "1_1") (pintype "passive"))
      (node (ref "C23") (pin "1") (pinfunction "1_1") (pintype "passive"))
      (node (ref "C24") (pin "1") (pinfunction "1_1") (pintype "passive"))
      (node (ref "R19") (pin "2") (pinfunction "2_2") (pintype "passive"))
      (node (ref "U5") (pin "15") (pinfunction "VDD_15") (pintype "passive"))
      (node (ref "U5") (pin "18") (pinfunction "VDD_18") (pintype "passive"))
      (node (ref "U5") (pin "19") (pinfunction "DVDD_19") (pintype "passive"))
      (node (ref "U5") (pin "7") (pinfunction "VDD_7") (pintype "passive"))
    )
    (net (code "65") (name "RF_GND") (class "Default")
      (node (ref "C21") (pin "2") (pinfunction "2_2") (pintype "passive"))
      (node (ref "C22") (pin "2") (pinfunction "2_2") (pintype "passive"))
      (node (ref "C23") (pin "2") (pinfunction "2_2") (pintype "passive"))
      (node (ref "C24") (pin "2") (pinfunction "2_2") (pintype "passive"))
      (node (ref "C29") (pin "1") (pinfunction "1_1") (pintype "passive"))
      (node (ref "C32") (pin "1") (pinfunction "1_1") (pintype "passive"))
      (node (ref "C33") (pin "1") (pinfunction "1_1") (pintype "passive"))
      (node (ref "C35") (pin "1") (pinfunction "1_1") (pintype "passive"))
      (node (ref "C36") (pin "1") (pinfunction "1_1") (pintype "passive"))
      (node (ref "R13") (pin "2") (pinfunction "2_2") (pintype "passive"))
      (node (ref "R18") (pin "2") (pinfunction "2_2") (pintype "passive"))
      (node (ref "U5") (pin "14") (pinfunction "VSS_14") (pintype "passive"))
      (node (ref "U5") (pin "17") (pinfunction "VSS_17") (pintype "passive"))
      (node (ref "U5") (pin "20") (pinfunction "VSS_20") (pintype "passive"))
      (node (ref "U5") (pin "8") (pinfunction "VSS_8") (pintype "passive"))
      (node (ref "Y2") (pin "2") (pinfunction "NC_2") (pintype "passive"))
      (node (ref "Y2") (pin "4") (pinfunction "NC_4") (pintype "passive"))
    )
    (net (code "66") (name "VBAT") (class "Default")
      (node (ref "C17") (pin "2") (pinfunction "2_2") (pintype "passive"))
      (node (ref "C18") (pin "2") (pinfunction "2_2") (pintype "passive"))
      (node (ref "C27") (pin "2") (pinfunction "2_2") (pintype "passive"))
      (node (ref "C28") (pin "2") (pinfunction "2_2") (pintype "passive"))
      (node (ref "C5") (pin "1") (pinfunction "1_1") (pintype "passive"))
      (node (ref "L1") (pin "1") (pinfunction "1_1") (pintype "passive"))
      (node (ref "M1") (pin "1") (pinfunction "1_1") (pintype "passive"))
      (node (ref "M2") (pin "1") (pinfunction "1_1") (pintype "passive"))
      (node (ref "M3") (pin "1") (pinfunction "1_1") (pintype "passive"))
      (node (ref "M4") (pin "1") (pinfunction "1_1") (pintype "passive"))
      (node (ref "R4") (pin "2") (pinfunction "2_2") (pintype "passive"))
      (node (ref "S1") (pin "2") (pinfunction "2_2") (pintype "passive"))
    )
    (net (code "67") (name "unconnected-(D5-DO-Pad4)") (class "Default")
      (node (ref "D5") (pin "4") (pinfunction "DO_4") (pintype "passive+no_connect"))
    )
    (net (code "68") (name "unconnected-(S1-Pad3)") (class "Default")
      (node (ref "S1") (pin "3") (pinfunction "3_3") (pintype "passive+no_connect"))
    )
    (net (code "69") (name "unconnected-(U3-PA0-Pad10)") (class "Default")
      (node (ref "U3") (pin "10") (pinfunction "PA0_10") (pintype "passive+no_connect"))
    )
    (net (code "70") (name "unconnected-(U3-PA15-Pad38)") (class "Default")
      (node (ref "U3") (pin "38") (pinfunction "PA15_38") (pintype "passive+no_connect"))
    )
    (net (code "71") (name "unconnected-(U3-PB3-Pad39)") (class "Default")
      (node (ref "U3") (pin "39") (pinfunction "PB3_39") (pintype "passive+no_connect"))
    )
    (net (code "72") (name "unconnected-(U3-PB4-Pad40)") (class "Default")
      (node (ref "U3") (pin "40") (pinfunction "PB4_40") (pintype "passive+no_connect"))
    )
    (net (code "73") (name "unconnected-(U3-PC15-Pad4)") (class "Default")
      (node (ref "U3") (pin "4") (pinfunction "PC15_4") (pintype "passive+no_connect"))
    )
    (net (code "74") (name "unconnected-(U4-A-CL-Pad7)") (class "Default")
      (node (ref "U4") (pin "7") (pinfunction "A-CL_7") (pintype "passive+no_connect"))
    )
    (net (code "75") (name "unconnected-(U4-A_DA-Pad6)") (class "Default")
      (node (ref "U4") (pin "6") (pinfunction "A_DA_6") (pintype "passive+no_connect"))
    )
    (net (code "76") (name "unconnected-(U4-CLKOUT-Pad22)") (class "Default")
      (node (ref "U4") (pin "22") (pinfunction "CLKOUT_22") (pintype "passive+no_connect"))
    )
    (net (code "77") (name "unconnected-(U4-NC-Pad2)") (class "Default")
      (node (ref "U4") (pin "2") (pinfunction "NC_2") (pintype "passive+no_connect"))
    )
    (net (code "78") (name "unconnected-(U4-NC-Pad3)") (class "Default")
      (node (ref "U4") (pin "3") (pinfunction "NC_3") (pintype "passive+no_connect"))
    )
    (net (code "79") (name "unconnected-(U4-NC-Pad4)") (class "Default")
      (node (ref "U4") (pin "4") (pinfunction "NC_4") (pintype "passive+no_connect"))
    )
    (net (code "80") (name "unconnected-(U4-NC-Pad5)") (class "Default")
      (node (ref "U4") (pin "5") (pinfunction "NC_5") (pintype "passive+no_connect"))
    )
    (net (code "81") (name "unconnected-(U4-NC-Pad14)") (class "Default")
      (node (ref "U4") (pin "14") (pinfunction "NC_14") (pintype "passive+no_connect"))
    )
    (net (code "82") (name "unconnected-(U4-NC-Pad15)") (class "Default")
      (node (ref "U4") (pin "15") (pinfunction "NC_15") (pintype "passive+no_connect"))
    )
    (net (code "83") (name "unconnected-(U4-NC-Pad16)") (class "Default")
      (node (ref "U4") (pin "16") (pinfunction "NC_16") (pintype "passive+no_connect"))
    )
    (net (code "84") (name "unconnected-(U4-NC-Pad17)") (class "Default")
      (node (ref "U4") (pin "17") (pinfunction "NC_17") (pintype "passive+no_connect"))
    )
    (net (code "85") (name "unconnected-(U4-RESV-Pad19)") (class "Default")
      (node (ref "U4") (pin "19") (pinfunction "RESV_19") (pintype "passive+no_connect"))
    )
    (net (code "86") (name "unconnected-(U4-RESV-Pad21)") (class "Default")
      (node (ref "U4") (pin "21") (pinfunction "RESV_21") (pintype "passive+no_connect"))
    )
  )
)
